# INKEY.net
KiCad netlist of a schematic drawn in Altium Designer
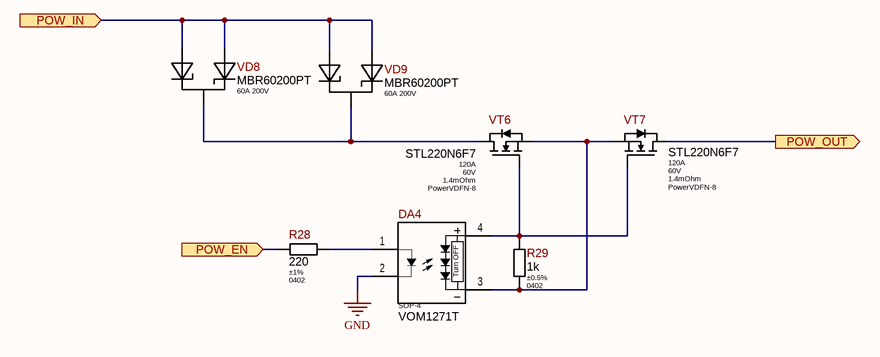
[diagram p0: INKEY.SchDoc]

(export (version "E")
  (design (tool "Eeschema 10.0.6"))
  (components
    (comp (ref "DA4")
      (value "VOM1271T")
      (footprint "SOP-4P254_492X720X222L65X51N")
      (description "Photovoltaic MOSFET Driver with Integrated Fast Turn-Off, 3750 VRMS")
      (fields
        (field (name "PACKAGE") "SOP-4")
        (field (name "PART NUMBER") "VOM1271T")
        (field (name "MANUFACTURER") "Vishay Semiconductors")
      )
      (libsource (lib "AjaxLibrary") (part "VOM1271T"))
    )
    (comp (ref "R28")
      (value "220")
      (footprint "R_ANY_CHIP_0402_MED")
      (description "220 Ohms ±1% 1/16W 0402 Thick Film Resistor")
      (fields
        (field (name "TOLERANCE") "±1%")
        (field (name "PACKAGE") "0402")
        (field (name "PART NUMBER") "RC0402FR-07220RL")
        (field (name "MANUFACTURER") "Yageo")
      )
      (libsource (lib "AjaxLibrary") (part "Resistor"))
    )
    (comp (ref "R29")
      (value "1k")
      (footprint "R_ANY_CHIP_0402_MED")
      (description "1 kOhms ±0.5% 1/16W 0402 Thick Film Resistor")
      (fields
        (field (name "TOLERANCE") "±0.5%")
        (field (name "PACKAGE") "0402")
        (field (name "PART NUMBER") "RC0402DR-071KL")
        (field (name "MANUFACTURER") "Yageo")
      )
      (libsource (lib "AjaxLibrary") (part "Resistor"))
    )
    (comp (ref "VD8")
      (value "MBR60200PT")
      (footprint "TO220-AB-H")
      (description "DIODE ARR SCHOT 200V 30A TO247-3")
      (fields (field (name "POWER RATING") "60A 200V") (field (name "MANUFACTURER") "Micro Commercial Co"))
      (libsource (lib "Database") (part "DUAL_DIODE"))
    )
    (comp (ref "VD9")
      (value "MBR60200PT")
      (footprint "TO220-AB-H")
      (description "DIODE ARR SCHOT 200V 30A TO247-3")
      (fields (field (name "POWER RATING") "60A 200V") (field (name "MANUFACTURER") "Micro Commercial Co"))
      (libsource (lib "Database") (part "DUAL_DIODE"))
    )
    (comp (ref "VT6")
      (value "STL220N6F7")
      (footprint "VSONP-CLIP-8_5.0x6.00mm")
      (description "60V, 120A max N-Channel Power MOSFET, 1.2mOhm @ Vgs = 10V")
      (fields
        (field (name "PART NUMBER") "STL220N6F7")
        (field (name "ID") "120A")
        (field (name "VDS") "60V")
        (field (name "RDS") "1.4mOhm")
        (field (name "PACKAGE") "PowerVDFN-8")
        (field (name "MANUFACTURER") "STMicroelectronics")
      )
      (libsource (lib "AjaxLibrary") (part "MOSFET-N-Channel-(GSD)"))
    )
    (comp (ref "VT7")
      (value "STL220N6F7")
      (footprint "VSONP-CLIP-8_5.0x6.00mm")
      (description "60V, 120A max N-Channel Power MOSFET, 1.2mOhm @ Vgs = 10V")
      (fields
        (field (name "PART NUMBER") "STL220N6F7")
        (field (name "ID") "120A")
        (field (name "VDS") "60V")
        (field (name "RDS") "1.4mOhm")
        (field (name "PACKAGE") "PowerVDFN-8")
        (field (name "MANUFACTURER") "STMicroelectronics")
      )
      (libsource (lib "AjaxLibrary") (part "MOSFET-N-Channel-(GSD)"))
    )
  )
  (nets
    (net (code "1") (name "/POW_EN") (class "Default") (node (ref "R28") (pin "1") (pintype "passive")))
    (net (code "2") (name "/POW_IN") (class "Default")
      (node (ref "VD8") (pin "1") (pintype "passive"))
      (node (ref "VD8") (pin "3") (pintype "passive"))
      (node (ref "VD9") (pin "1") (pintype "passive"))
      (node (ref "VD9") (pin "3") (pintype "passive"))
    )
    (net (code "3") (name "/POW_OUT") (class "Default")
      (node (ref "VT7") (pin "D") (pinfunction "Drain_D") (pintype "passive"))
    )
    (net (code "4") (name "GND") (class "Default")
      (node (ref "DA4") (pin "2") (pinfunction "Cathode_2") (pintype "passive"))
    )
    (net (code "5") (name "Net-(DA4-Anode)") (class "Default")
      (node (ref "DA4") (pin "1") (pinfunction "Anode_1") (pintype "passive"))
      (node (ref "R28") (pin "2") (pintype "passive"))
    )
    (net (code "6") (name "Net-(DA4-Collector)") (class "Default")
      (node (ref "DA4") (pin "4") (pinfunction "Collector_4") (pintype "passive"))
      (node (ref "R29") (pin "1") (pintype "passive"))
      (node (ref "VT6") (pin "G") (pinfunction "Gate_G") (pintype "passive"))
      (node (ref "VT7") (pin "G") (pinfunction "Gate_G") (pintype "passive"))
    )
    (net (code "7") (name "Net-(DA4-Emitter)") (class "Default")
      (node (ref "DA4") (pin "3") (pinfunction "Emitter_3") (pintype "passive"))
      (node (ref "R29") (pin "2") (pintype "passive"))
      (node (ref "VT6") (pin "S") (pinfunction "Source_S") (pintype "passive"))
      (node (ref "VT7") (pin "S") (pinfunction "Source_S") (pintype "passive"))
    )
    (net (code "8") (name "Net-(VT6-Drain)") (class "Default")
      (node (ref "VD8") (pin "2") (pintype "passive"))
      (node (ref "VD9") (pin "2") (pintype "passive"))
      (node (ref "VT6") (pin "D") (pinfunction "Drain_D") (pintype "passive"))
    )
  )
)
